# Schematic_1.net
KiCad netlist of a schematic drawn in EAGLE
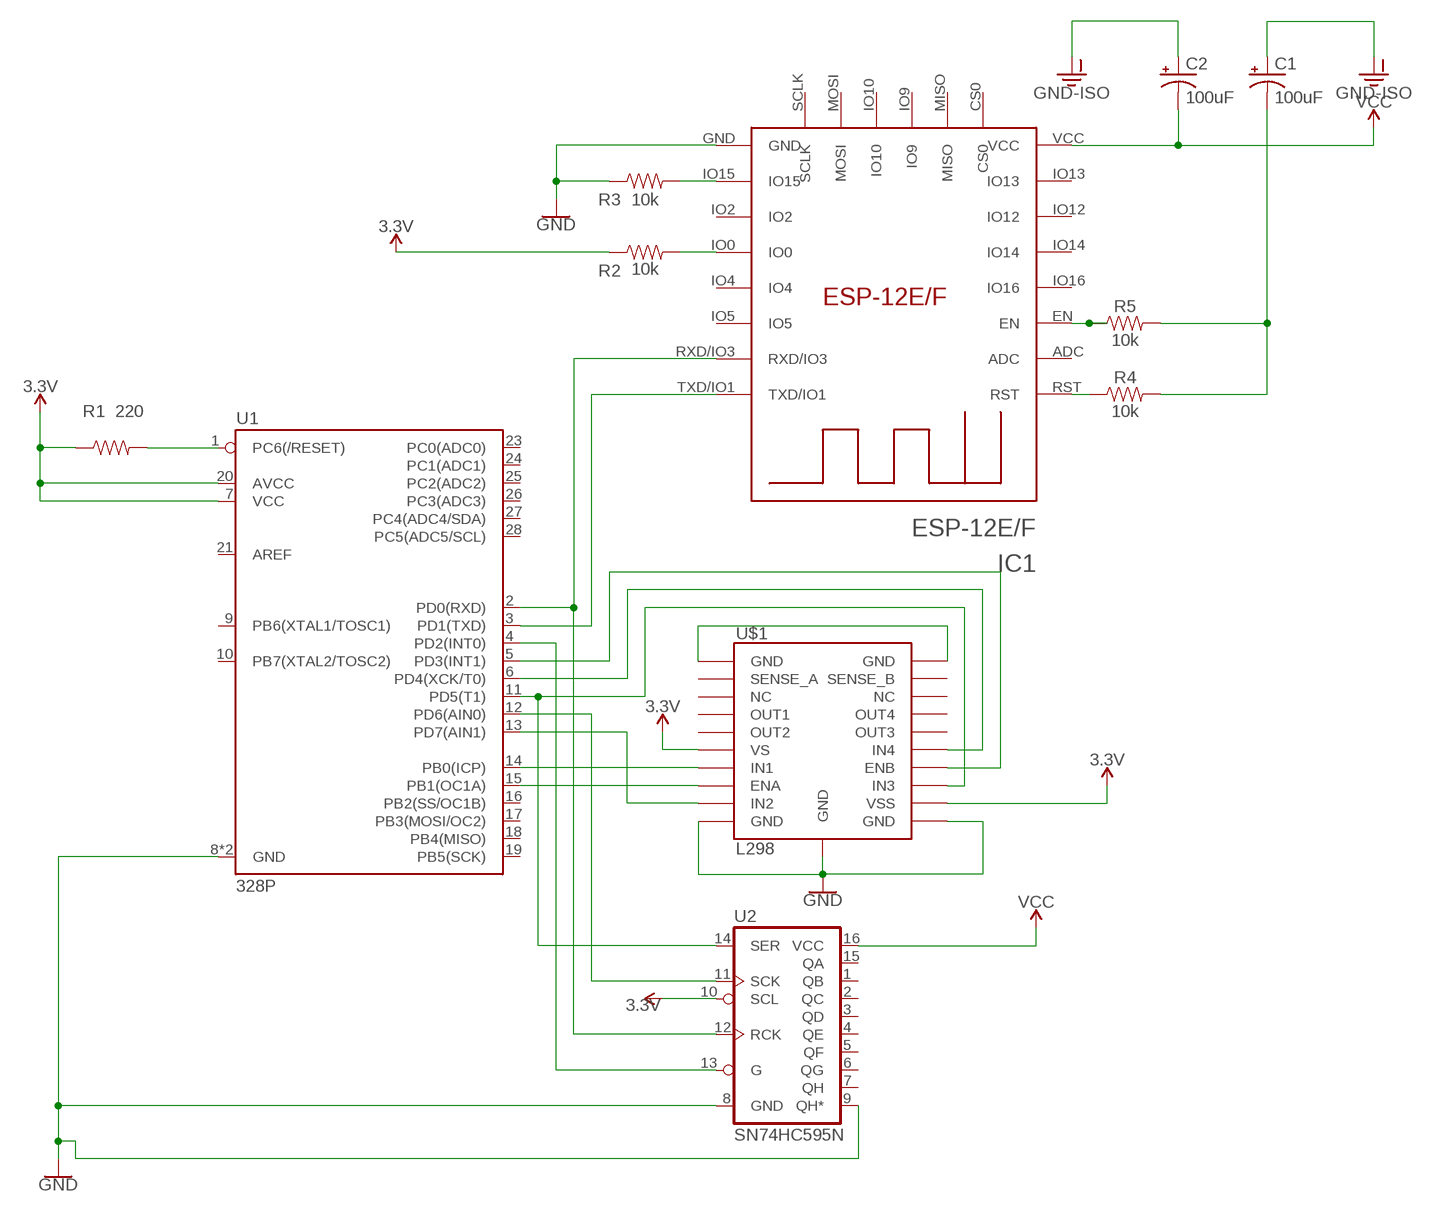
[diagram p0: schematic, sheet 1]

(export (version "E")
  (design (tool "Eeschema 10.0.6"))
  (components
    (comp (ref "C1")
      (value "100uF")
      (footprint "eagle-import:CPOL-RADIAL-2.5MM-6.5MM")
      (libsource (lib "eagle-import") (part "100UF-POLAR-RADIAL-2.5MM-25V-20%"))
    )
    (comp (ref "C2")
      (value "100uF")
      (footprint "eagle-import:CPOL-RADIAL-2.5MM-6.5MM")
      (libsource (lib "eagle-import") (part "100UF-POLAR-RADIAL-2.5MM-25V-20%"))
    )
    (comp (ref "IC1")
      (value "ESP-12E/F")
      (footprint "eagle-import:ESP-12E")
      (libsource (lib "eagle-import") (part "ESP-12E/F"))
    )
    (comp (ref "R1")
      (value "220")
      (footprint "eagle-import:0603")
      (libsource (lib "eagle-import") (part "220OHM-0603-1/10W-1%"))
    )
    (comp (ref "R2")
      (value "10k")
      (footprint "eagle-import:AXIAL-0.3")
      (libsource (lib "eagle-import") (part "10KOHM-HORIZ-1/4W-1%"))
    )
    (comp (ref "R3")
      (value "10k")
      (footprint "eagle-import:AXIAL-0.3")
      (libsource (lib "eagle-import") (part "10KOHM-HORIZ-1/4W-1%"))
    )
    (comp (ref "R4")
      (value "10k")
      (footprint "eagle-import:AXIAL-0.3")
      (libsource (lib "eagle-import") (part "10KOHM-HORIZ-1/4W-1%"))
    )
    (comp (ref "R5")
      (value "10k")
      (footprint "eagle-import:AXIAL-0.3")
      (libsource (lib "eagle-import") (part "10KOHM-HORIZ-1/4W-1%"))
    )
    (comp (ref "U$1")
      (value "L298")
      (footprint "eagle-import:POWERSO20_L298_PAD")
      (libsource (lib "eagle-import") (part "L298_SMD_W_PAD"))
    )
    (comp (ref "U1")
      (value "328P")
      (footprint "eagle-import:DIP28")
      (libsource (lib "eagle-import") (part "ATMEGA328P_PDIP"))
    )
    (comp (ref "U2")
      (value "SN74HC595N")
      (footprint "eagle-import:DIP16")
      (libsource (lib "eagle-import") (part "74595NHC"))
    )
  )
  (nets
    (net (code "1") (name "3.3V") (class "Default")
      (node (ref "R1") (pin "1") (pinfunction "1_1") (pintype "passive"))
      (node (ref "R2") (pin "P$1") (pinfunction "1_P$1") (pintype "passive"))
      (node (ref "U$1") (pin "12") (pinfunction "VSS_12") (pintype "bidirectional"))
      (node (ref "U$1") (pin "6") (pinfunction "VS_6") (pintype "bidirectional"))
      (node (ref "U1") (pin "20") (pinfunction "AVCC_20") (pintype "bidirectional"))
      (node (ref "U1") (pin "7") (pinfunction "VCC_7") (pintype "bidirectional"))
      (node (ref "U2") (pin "10") (pinfunction "SCL_10") (pintype "input"))
    )
    (net (code "2") (name "GND") (class "Default")
      (node (ref "IC1") (pin "GND") (pinfunction "GND_GND") (pintype "power_in"))
      (node (ref "R3") (pin "P$1") (pinfunction "1_P$1") (pintype "passive"))
      (node (ref "U$1") (pin "10") (pinfunction "GND_10") (pintype "bidirectional"))
      (node (ref "U$1") (pin "11") (pinfunction "GND_11") (pintype "bidirectional"))
      (node (ref "U$1") (pin "PAD") (pinfunction "GND_PAD") (pintype "bidirectional"))
      (node (ref "U1") (pin "22") (pinfunction "GND_22") (pintype "bidirectional"))
      (node (ref "U1") (pin "8") (pinfunction "GND_8") (pintype "bidirectional"))
      (node (ref "U2") (pin "8") (pinfunction "GND_8") (pintype "power_in"))
      (node (ref "U2") (pin "9") (pinfunction "QH*_9") (pintype "tri_state"))
    )
    (net (code "3") (name "GND-ISO") (class "Default")
      (node (ref "C1") (pin "1") (pinfunction "+_1") (pintype "passive"))
      (node (ref "C2") (pin "1") (pinfunction "+_1") (pintype "passive"))
    )
    (net (code "4") (name "Net-(C1--)") (class "Default")
      (node (ref "C1") (pin "2") (pinfunction "-_2") (pintype "passive"))
      (node (ref "R4") (pin "P$2") (pinfunction "2_P$2") (pintype "passive"))
      (node (ref "R5") (pin "P$2") (pinfunction "2_P$2") (pintype "passive"))
    )
    (net (code "5") (name "Net-(R2-2)") (class "Default")
      (node (ref "IC1") (pin "IO0") (pinfunction "IO0_IO0") (pintype "bidirectional"))
      (node (ref "R2") (pin "P$2") (pinfunction "2_P$2") (pintype "passive"))
    )
    (net (code "6") (name "Net-(R3-2)") (class "Default")
      (node (ref "IC1") (pin "IO15") (pinfunction "IO15_IO15") (pintype "bidirectional"))
      (node (ref "R3") (pin "P$2") (pinfunction "2_P$2") (pintype "passive"))
    )
    (net (code "7") (name "Net-(R4-1)") (class "Default")
      (node (ref "IC1") (pin "RST") (pinfunction "RST_RST") (pintype "input"))
      (node (ref "R4") (pin "P$1") (pinfunction "1_P$1") (pintype "passive"))
    )
    (net (code "8") (name "Net-(R5-1)") (class "Default")
      (node (ref "IC1") (pin "EN") (pinfunction "EN_EN") (pintype "bidirectional"))
      (node (ref "R5") (pin "P$1") (pinfunction "1_P$1") (pintype "passive"))
    )
    (net (code "9") (name "Net-(U$1-ENA)") (class "Default")
      (node (ref "U$1") (pin "8") (pinfunction "ENA_8") (pintype "bidirectional"))
      (node (ref "U1") (pin "15") (pinfunction "PB1(OC1A)_15") (pintype "bidirectional"))
    )
    (net (code "10") (name "Net-(U$1-ENB)") (class "Default")
      (node (ref "U$1") (pin "14") (pinfunction "ENB_14") (pintype "bidirectional"))
      (node (ref "U1") (pin "5") (pinfunction "PD3(INT1)_5") (pintype "bidirectional"))
    )
    (net (code "11") (name "Net-(U$1-GND-Pad1)") (class "Default")
      (node (ref "U$1") (pin "1") (pinfunction "GND_1") (pintype "bidirectional"))
      (node (ref "U$1") (pin "20") (pinfunction "GND_20") (pintype "bidirectional"))
    )
    (net (code "12") (name "Net-(U$1-IN1)") (class "Default")
      (node (ref "U$1") (pin "7") (pinfunction "IN1_7") (pintype "bidirectional"))
      (node (ref "U1") (pin "14") (pinfunction "PB0(ICP)_14") (pintype "bidirectional"))
    )
    (net (code "13") (name "Net-(U$1-IN2)") (class "Default")
      (node (ref "U$1") (pin "9") (pinfunction "IN2_9") (pintype "bidirectional"))
      (node (ref "U1") (pin "13") (pinfunction "PD7(AIN1)_13") (pintype "bidirectional"))
    )
    (net (code "14") (name "Net-(U$1-IN3)") (class "Default")
      (node (ref "U$1") (pin "13") (pinfunction "IN3_13") (pintype "bidirectional"))
      (node (ref "U1") (pin "11") (pinfunction "PD5(T1)_11") (pintype "bidirectional"))
      (node (ref "U2") (pin "14") (pinfunction "SER_14") (pintype "input"))
    )
    (net (code "15") (name "Net-(U$1-IN4)") (class "Default")
      (node (ref "U$1") (pin "15") (pinfunction "IN4_15") (pintype "bidirectional"))
      (node (ref "U1") (pin "6") (pinfunction "PD4(XCK/T0)_6") (pintype "bidirectional"))
    )
    (net (code "16") (name "Net-(U1-PC6({slash}RESET))") (class "Default")
      (node (ref "R1") (pin "2") (pinfunction "2_2") (pintype "passive"))
      (node (ref "U1") (pin "1") (pinfunction "PC6(/RESET)_1") (pintype "bidirectional"))
    )
    (net (code "17") (name "Net-(U1-PD0(RXD))") (class "Default")
      (node (ref "IC1") (pin "RXD/IO3") (pinfunction "RXD/IO3_RXD/IO3") (pintype "bidirectional"))
      (node (ref "U1") (pin "2") (pinfunction "PD0(RXD)_2") (pintype "bidirectional"))
      (node (ref "U2") (pin "12") (pinfunction "RCK_12") (pintype "input"))
    )
    (net (code "18") (name "Net-(U1-PD1(TXD))") (class "Default")
      (node (ref "IC1") (pin "TXD/IO1") (pinfunction "TXD/IO1_TXD/IO1") (pintype "bidirectional"))
      (node (ref "U1") (pin "3") (pinfunction "PD1(TXD)_3") (pintype "bidirectional"))
    )
    (net (code "19") (name "Net-(U1-PD2(INT0))") (class "Default")
      (node (ref "U1") (pin "4") (pinfunction "PD2(INT0)_4") (pintype "bidirectional"))
      (node (ref "U2") (pin "13") (pinfunction "G_13") (pintype "input"))
    )
    (net (code "20") (name "Net-(U1-PD6(AIN0))") (class "Default")
      (node (ref "U1") (pin "12") (pinfunction "PD6(AIN0)_12") (pintype "bidirectional"))
      (node (ref "U2") (pin "11") (pinfunction "SCK_11") (pintype "input"))
    )
    (net (code "21") (name "VCC") (class "Default")
      (node (ref "C2") (pin "2") (pinfunction "-_2") (pintype "passive"))
      (node (ref "IC1") (pin "VCC") (pinfunction "VCC_VCC") (pintype "power_in"))
      (node (ref "U2") (pin "16") (pinfunction "VCC_16") (pintype "power_in"))
    )
    (net (code "22") (name "unconnected-(IC1-PadADC)") (class "Default")
      (node (ref "IC1") (pin "ADC") (pinfunction "ADC_ADC") (pintype "bidirectional"))
    )
    (net (code "23") (name "unconnected-(IC1-PadCS0)") (class "Default")
      (node (ref "IC1") (pin "CS0") (pinfunction "CS0_CS0") (pintype "bidirectional"))
    )
    (net (code "24") (name "unconnected-(IC1-PadIO2)") (class "Default")
      (node (ref "IC1") (pin "IO2") (pinfunction "IO2_IO2") (pintype "bidirectional"))
    )
    (net (code "25") (name "unconnected-(IC1-PadIO4)") (class "Default")
      (node (ref "IC1") (pin "IO4") (pinfunction "IO4_IO4") (pintype "bidirectional"))
    )
    (net (code "26") (name "unconnected-(IC1-PadIO5)") (class "Default")
      (node (ref "IC1") (pin "IO5") (pinfunction "IO5_IO5") (pintype "bidirectional"))
    )
    (net (code "27") (name "unconnected-(IC1-PadIO9)") (class "Default")
      (node (ref "IC1") (pin "IO9") (pinfunction "IO9_IO9") (pintype "bidirectional"))
    )
    (net (code "28") (name "unconnected-(IC1-PadIO10)") (class "Default")
      (node (ref "IC1") (pin "IO10") (pinfunction "IO10_IO10") (pintype "bidirectional"))
    )
    (net (code "29") (name "unconnected-(IC1-PadIO12)") (class "Default")
      (node (ref "IC1") (pin "IO12") (pinfunction "IO12_IO12") (pintype "bidirectional"))
    )
    (net (code "30") (name "unconnected-(IC1-PadIO13)") (class "Default")
      (node (ref "IC1") (pin "IO13") (pinfunction "IO13_IO13") (pintype "bidirectional"))
    )
    (net (code "31") (name "unconnected-(IC1-PadIO14)") (class "Default")
      (node (ref "IC1") (pin "IO14") (pinfunction "IO14_IO14") (pintype "bidirectional"))
    )
    (net (code "32") (name "unconnected-(IC1-PadIO16)") (class "Default")
      (node (ref "IC1") (pin "IO16") (pinfunction "IO16_IO16") (pintype "bidirectional"))
    )
    (net (code "33") (name "unconnected-(IC1-PadMISO)") (class "Default")
      (node (ref "IC1") (pin "MISO") (pinfunction "MISO_MISO") (pintype "bidirectional"))
    )
    (net (code "34") (name "unconnected-(IC1-PadMOSI)") (class "Default")
      (node (ref "IC1") (pin "MOSI") (pinfunction "MOSI_MOSI") (pintype "bidirectional"))
    )
    (net (code "35") (name "unconnected-(IC1-PadSCLK)") (class "Default")
      (node (ref "IC1") (pin "SCLK") (pinfunction "SCLK_SCLK") (pintype "bidirectional"))
    )
    (net (code "36") (name "unconnected-(U$1-NC-Pad3)") (class "Default")
      (node (ref "U$1") (pin "3") (pinfunction "NC_3") (pintype "bidirectional"))
    )
    (net (code "37") (name "unconnected-(U$1-NC-Pad18)") (class "Default")
      (node (ref "U$1") (pin "18") (pinfunction "NC_18") (pintype "bidirectional"))
    )
    (net (code "38") (name "unconnected-(U$1-OUT1-Pad4)") (class "Default")
      (node (ref "U$1") (pin "4") (pinfunction "OUT1_4") (pintype "bidirectional"))
    )
    (net (code "39") (name "unconnected-(U$1-OUT2-Pad5)") (class "Default")
      (node (ref "U$1") (pin "5") (pinfunction "OUT2_5") (pintype "bidirectional"))
    )
    (net (code "40") (name "unconnected-(U$1-OUT3-Pad16)") (class "Default")
      (node (ref "U$1") (pin "16") (pinfunction "OUT3_16") (pintype "bidirectional"))
    )
    (net (code "41") (name "unconnected-(U$1-OUT4-Pad17)") (class "Default")
      (node (ref "U$1") (pin "17") (pinfunction "OUT4_17") (pintype "bidirectional"))
    )
    (net (code "42") (name "unconnected-(U$1-SENSE_A-Pad2)") (class "Default")
      (node (ref "U$1") (pin "2") (pinfunction "SENSE_A_2") (pintype "bidirectional"))
    )
    (net (code "43") (name "unconnected-(U$1-SENSE_B-Pad19)") (class "Default")
      (node (ref "U$1") (pin "19") (pinfunction "SENSE_B_19") (pintype "bidirectional"))
    )
    (net (code "44") (name "unconnected-(U1-AREF-Pad21)") (class "Default")
      (node (ref "U1") (pin "21") (pinfunction "AREF_21") (pintype "bidirectional"))
    )
    (net (code "45") (name "unconnected-(U1-PB2(SS{slash}OC1B)-Pad16)") (class "Default")
      (node (ref "U1") (pin "16") (pinfunction "PB2(SS/OC1B)_16") (pintype "bidirectional"))
    )
    (net (code "46") (name "unconnected-(U1-PB3(MOSI{slash}OC2)-Pad17)") (class "Default")
      (node (ref "U1") (pin "17") (pinfunction "PB3(MOSI/OC2)_17") (pintype "bidirectional"))
    )
    (net (code "47") (name "unconnected-(U1-PB4(MISO)-Pad18)") (class "Default")
      (node (ref "U1") (pin "18") (pinfunction "PB4(MISO)_18") (pintype "bidirectional"))
    )
    (net (code "48") (name "unconnected-(U1-PB5(SCK)-Pad19)") (class "Default")
      (node (ref "U1") (pin "19") (pinfunction "PB5(SCK)_19") (pintype "bidirectional"))
    )
    (net (code "49") (name "unconnected-(U1-PB6(XTAL1{slash}TOSC1)-Pad9)") (class "Default")
      (node (ref "U1") (pin "9") (pinfunction "PB6(XTAL1/TOSC1)_9") (pintype "bidirectional"))
    )
    (net (code "50") (name "unconnected-(U1-PB7(XTAL2{slash}TOSC2)-Pad10)") (class "Default")
      (node (ref "U1") (pin "10") (pinfunction "PB7(XTAL2/TOSC2)_10") (pintype "bidirectional"))
    )
    (net (code "51") (name "unconnected-(U1-PC0(ADC0)-Pad23)") (class "Default")
      (node (ref "U1") (pin "23") (pinfunction "PC0(ADC0)_23") (pintype "bidirectional"))
    )
    (net (code "52") (name "unconnected-(U1-PC1(ADC1)-Pad24)") (class "Default")
      (node (ref "U1") (pin "24") (pinfunction "PC1(ADC1)_24") (pintype "bidirectional"))
    )
    (net (code "53") (name "unconnected-(U1-PC2(ADC2)-Pad25)") (class "Default")
      (node (ref "U1") (pin "25") (pinfunction "PC2(ADC2)_25") (pintype "bidirectional"))
    )
    (net (code "54") (name "unconnected-(U1-PC3(ADC3)-Pad26)") (class "Default")
      (node (ref "U1") (pin "26") (pinfunction "PC3(ADC3)_26") (pintype "bidirectional"))
    )
    (net (code "55") (name "unconnected-(U1-PC4(ADC4{slash}SDA)-Pad27)") (class "Default")
      (node (ref "U1") (pin "27") (pinfunction "PC4(ADC4/SDA)_27") (pintype "bidirectional"))
    )
    (net (code "56") (name "unconnected-(U1-PC5(ADC5{slash}SCL)-Pad28)") (class "Default")
      (node (ref "U1") (pin "28") (pinfunction "PC5(ADC5/SCL)_28") (pintype "bidirectional"))
    )
    (net (code "57") (name "unconnected-(U2-QA-Pad15)") (class "Default")
      (node (ref "U2") (pin "15") (pinfunction "QA_15") (pintype "tri_state"))
    )
    (net (code "58") (name "unconnected-(U2-QB-Pad1)") (class "Default")
      (node (ref "U2") (pin "1") (pinfunction "QB_1") (pintype "tri_state"))
    )
    (net (code "59") (name "unconnected-(U2-QC-Pad2)") (class "Default")
      (node (ref "U2") (pin "2") (pinfunction "QC_2") (pintype "tri_state"))
    )
    (net (code "60") (name "unconnected-(U2-QD-Pad3)") (class "Default")
      (node (ref "U2") (pin "3") (pinfunction "QD_3") (pintype "tri_state"))
    )
    (net (code "61") (name "unconnected-(U2-QE-Pad4)") (class "Default")
      (node (ref "U2") (pin "4") (pinfunction "QE_4") (pintype "tri_state"))
    )
    (net (code "62") (name "unconnected-(U2-QF-Pad5)") (class "Default")
      (node (ref "U2") (pin "5") (pinfunction "QF_5") (pintype "tri_state"))
    )
    (net (code "63") (name "unconnected-(U2-QG-Pad6)") (class "Default")
      (node (ref "U2") (pin "6") (pinfunction "QG_6") (pintype "tri_state"))
    )
    (net (code "64") (name "unconnected-(U2-QH-Pad7)") (class "Default")
      (node (ref "U2") (pin "7") (pinfunction "QH_7") (pintype "tri_state"))
    )
  )
)
